# Skaarhoj_BI8-1x8slim.net
KiCad netlist of a schematic drawn in EAGLE
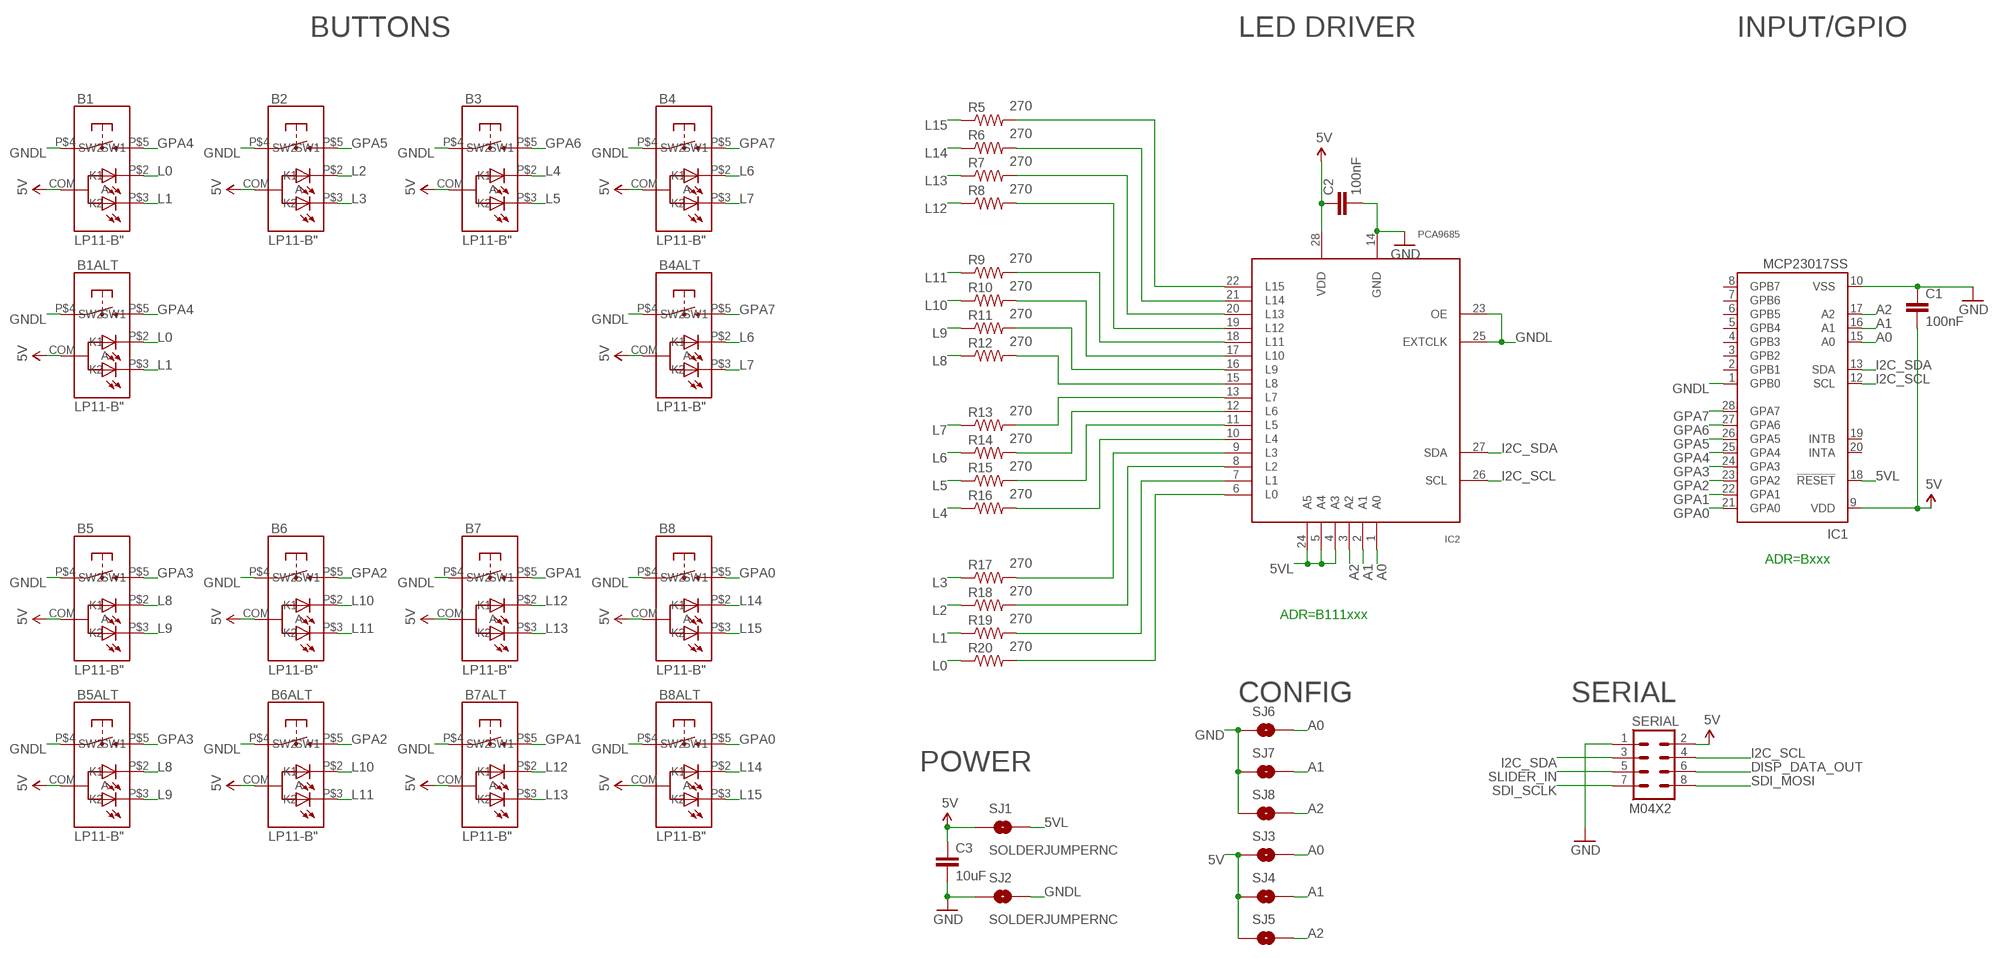
[diagram p0: schematic, sheet 1]

(export (version "E")
  (design (tool "Eeschema 10.0.6"))
  (components
    (comp (ref "B1")
      (value "LP11-B\"")
      (footprint "eagle-import:LP11")
      (libsource (lib "eagle-import") (part "LP11-B{dblquote}"))
    )
    (comp (ref "B1ALT")
      (value "LP11-B\"")
      (footprint "eagle-import:LP11")
      (libsource (lib "eagle-import") (part "LP11-B{dblquote}"))
    )
    (comp (ref "B2")
      (value "LP11-B\"")
      (footprint "eagle-import:LP11")
      (libsource (lib "eagle-import") (part "LP11-B{dblquote}"))
    )
    (comp (ref "B3")
      (value "LP11-B\"")
      (footprint "eagle-import:LP11")
      (libsource (lib "eagle-import") (part "LP11-B{dblquote}"))
    )
    (comp (ref "B4")
      (value "LP11-B\"")
      (footprint "eagle-import:LP11")
      (libsource (lib "eagle-import") (part "LP11-B{dblquote}"))
    )
    (comp (ref "B4ALT")
      (value "LP11-B\"")
      (footprint "eagle-import:LP11")
      (libsource (lib "eagle-import") (part "LP11-B{dblquote}"))
    )
    (comp (ref "B5")
      (value "LP11-B\"")
      (footprint "eagle-import:LP11")
      (libsource (lib "eagle-import") (part "LP11-B{dblquote}"))
    )
    (comp (ref "B5ALT")
      (value "LP11-B\"")
      (footprint "eagle-import:LP11")
      (libsource (lib "eagle-import") (part "LP11-B{dblquote}"))
    )
    (comp (ref "B6")
      (value "LP11-B\"")
      (footprint "eagle-import:LP11")
      (libsource (lib "eagle-import") (part "LP11-B{dblquote}"))
    )
    (comp (ref "B6ALT")
      (value "LP11-B\"")
      (footprint "eagle-import:LP11")
      (libsource (lib "eagle-import") (part "LP11-B{dblquote}"))
    )
    (comp (ref "B7")
      (value "LP11-B\"")
      (footprint "eagle-import:LP11")
      (libsource (lib "eagle-import") (part "LP11-B{dblquote}"))
    )
    (comp (ref "B7ALT")
      (value "LP11-B\"")
      (footprint "eagle-import:LP11")
      (libsource (lib "eagle-import") (part "LP11-B{dblquote}"))
    )
    (comp (ref "B8")
      (value "LP11-B\"")
      (footprint "eagle-import:LP11")
      (libsource (lib "eagle-import") (part "LP11-B{dblquote}"))
    )
    (comp (ref "B8ALT")
      (value "LP11-B\"")
      (footprint "eagle-import:LP11")
      (libsource (lib "eagle-import") (part "LP11-B{dblquote}"))
    )
    (comp (ref "C1")
      (value "100nF")
      (footprint "eagle-import:0603-CAP")
      (libsource (lib "eagle-import") (part "CAP0603-CAP"))
    )
    (comp (ref "C2")
      (value "100nF")
      (footprint "eagle-import:0603-CAP")
      (libsource (lib "eagle-import") (part "CAP0603-CAP"))
    )
    (comp (ref "C3")
      (value "10uF")
      (footprint "eagle-import:0805")
      (libsource (lib "eagle-import") (part "CAP0805"))
    )
    (comp (ref "IC1")
      (value "MCP23017SS")
      (footprint "eagle-import:SSOP28")
      (fields
        (field (name "MF") "MICROCHIP")
        (field (name "MPN") "MCP23017-E/SS")
        (field (name "MPN_1") "MCP23017-E/SS")
        (field (name "OC_FARNELL") "1467674")
        (field (name "OC_NEWARK") "31K2960")
      )
      (libsource (lib "eagle-import") (part "MCP23017SS"))
    )
    (comp (ref "IC2")
      (value "PCA9685")
      (footprint "eagle-import:TSSOP28")
      (libsource (lib "eagle-import") (part "PCA9685"))
    )
    (comp (ref "R5")
      (value "270")
      (footprint "eagle-import:0603-RES")
      (libsource (lib "eagle-import") (part "RESISTOR0603-RES"))
    )
    (comp (ref "R6")
      (value "270")
      (footprint "eagle-import:0603-RES")
      (libsource (lib "eagle-import") (part "RESISTOR0603-RES"))
    )
    (comp (ref "R7")
      (value "270")
      (footprint "eagle-import:0603-RES")
      (libsource (lib "eagle-import") (part "RESISTOR0603-RES"))
    )
    (comp (ref "R8")
      (value "270")
      (footprint "eagle-import:0603-RES")
      (libsource (lib "eagle-import") (part "RESISTOR0603-RES"))
    )
    (comp (ref "R9")
      (value "270")
      (footprint "eagle-import:0603-RES")
      (libsource (lib "eagle-import") (part "RESISTOR0603-RES"))
    )
    (comp (ref "R10")
      (value "270")
      (footprint "eagle-import:0603-RES")
      (libsource (lib "eagle-import") (part "RESISTOR0603-RES"))
    )
    (comp (ref "R11")
      (value "270")
      (footprint "eagle-import:0603-RES")
      (libsource (lib "eagle-import") (part "RESISTOR0603-RES"))
    )
    (comp (ref "R12")
      (value "270")
      (footprint "eagle-import:0603-RES")
      (libsource (lib "eagle-import") (part "RESISTOR0603-RES"))
    )
    (comp (ref "R13")
      (value "270")
      (footprint "eagle-import:0603-RES")
      (libsource (lib "eagle-import") (part "RESISTOR0603-RES"))
    )
    (comp (ref "R14")
      (value "270")
      (footprint "eagle-import:0603-RES")
      (libsource (lib "eagle-import") (part "RESISTOR0603-RES"))
    )
    (comp (ref "R15")
      (value "270")
      (footprint "eagle-import:0603-RES")
      (libsource (lib "eagle-import") (part "RESISTOR0603-RES"))
    )
    (comp (ref "R16")
      (value "270")
      (footprint "eagle-import:0603-RES")
      (libsource (lib "eagle-import") (part "RESISTOR0603-RES"))
    )
    (comp (ref "R17")
      (value "270")
      (footprint "eagle-import:0603-RES")
      (libsource (lib "eagle-import") (part "RESISTOR0603-RES"))
    )
    (comp (ref "R18")
      (value "270")
      (footprint "eagle-import:0603-RES")
      (libsource (lib "eagle-import") (part "RESISTOR0603-RES"))
    )
    (comp (ref "R19")
      (value "270")
      (footprint "eagle-import:0603-RES")
      (libsource (lib "eagle-import") (part "RESISTOR0603-RES"))
    )
    (comp (ref "R20")
      (value "270")
      (footprint "eagle-import:0603-RES")
      (libsource (lib "eagle-import") (part "RESISTOR0603-RES"))
    )
    (comp (ref "SERIAL")
      (value "M04X2")
      (footprint "eagle-import:2X4")
      (libsource (lib "eagle-import") (part "M04X2"))
    )
    (comp (ref "SJ1")
      (value "SOLDERJUMPERNC")
      (footprint "eagle-import:SJ_2S")
      (libsource (lib "eagle-import") (part "SOLDERJUMPERNC"))
    )
    (comp (ref "SJ2")
      (value "SOLDERJUMPERNC")
      (footprint "eagle-import:SJ_2S")
      (libsource (lib "eagle-import") (part "SOLDERJUMPERNC"))
    )
    (comp (ref "SJ3")
      (value "SOLDERJUMPERNC")
      (footprint "eagle-import:SJ_2S")
      (libsource (lib "eagle-import") (part "SOLDERJUMPERNC"))
    )
    (comp (ref "SJ4")
      (value "SOLDERJUMPERNC")
      (footprint "eagle-import:SJ_2S")
      (libsource (lib "eagle-import") (part "SOLDERJUMPERNC"))
    )
    (comp (ref "SJ5")
      (value "SOLDERJUMPERNC")
      (footprint "eagle-import:SJ_2S")
      (libsource (lib "eagle-import") (part "SOLDERJUMPERNC"))
    )
    (comp (ref "SJ6")
      (value "SOLDERJUMPERNC")
      (footprint "eagle-import:SJ_2S")
      (libsource (lib "eagle-import") (part "SOLDERJUMPERNC"))
    )
    (comp (ref "SJ7")
      (value "SOLDERJUMPERNC")
      (footprint "eagle-import:SJ_2S")
      (libsource (lib "eagle-import") (part "SOLDERJUMPERNC"))
    )
    (comp (ref "SJ8")
      (value "SOLDERJUMPERNC")
      (footprint "eagle-import:SJ_2S")
      (libsource (lib "eagle-import") (part "SOLDERJUMPERNC"))
    )
  )
  (nets
    (net (code "1") (name "/5VL") (class "Default")
      (node (ref "IC1") (pin "18") (pinfunction "~{RESET}_18") (pintype "input"))
      (node (ref "IC2") (pin "24") (pinfunction "A5_24") (pintype "input"))
      (node (ref "IC2") (pin "4") (pinfunction "A3_4") (pintype "input"))
      (node (ref "IC2") (pin "5") (pinfunction "A4_5") (pintype "input"))
      (node (ref "SJ1") (pin "2") (pinfunction "2_2") (pintype "passive"))
    )
    (net (code "2") (name "/A0") (class "Default")
      (node (ref "IC1") (pin "15") (pinfunction "A0_15") (pintype "input"))
      (node (ref "IC2") (pin "1") (pinfunction "A0_1") (pintype "input"))
      (node (ref "SJ3") (pin "2") (pinfunction "2_2") (pintype "passive"))
      (node (ref "SJ6") (pin "2") (pinfunction "2_2") (pintype "passive"))
    )
    (net (code "3") (name "/A1") (class "Default")
      (node (ref "IC1") (pin "16") (pinfunction "A1_16") (pintype "input"))
      (node (ref "IC2") (pin "2") (pinfunction "A1_2") (pintype "input"))
      (node (ref "SJ4") (pin "2") (pinfunction "2_2") (pintype "passive"))
      (node (ref "SJ7") (pin "2") (pinfunction "2_2") (pintype "passive"))
    )
    (net (code "4") (name "/A2") (class "Default")
      (node (ref "IC1") (pin "17") (pinfunction "A2_17") (pintype "input"))
      (node (ref "IC2") (pin "3") (pinfunction "A2_3") (pintype "input"))
      (node (ref "SJ5") (pin "2") (pinfunction "2_2") (pintype "passive"))
      (node (ref "SJ8") (pin "2") (pinfunction "2_2") (pintype "passive"))
    )
    (net (code "5") (name "/DISP_DATA_OUT") (class "Default")
      (node (ref "SERIAL") (pin "6") (pinfunction "6_6") (pintype "passive"))
    )
    (net (code "6") (name "/GNDL") (class "Default")
      (node (ref "B1") (pin "P$4") (pinfunction "SW1_P$4") (pintype "bidirectional"))
      (node (ref "B1ALT") (pin "P$4") (pinfunction "SW1_P$4") (pintype "bidirectional"))
      (node (ref "B2") (pin "P$4") (pinfunction "SW1_P$4") (pintype "bidirectional"))
      (node (ref "B3") (pin "P$4") (pinfunction "SW1_P$4") (pintype "bidirectional"))
      (node (ref "B4") (pin "P$4") (pinfunction "SW1_P$4") (pintype "bidirectional"))
      (node (ref "B4ALT") (pin "P$4") (pinfunction "SW1_P$4") (pintype "bidirectional"))
      (node (ref "B5") (pin "P$4") (pinfunction "SW1_P$4") (pintype "bidirectional"))
      (node (ref "B5ALT") (pin "P$4") (pinfunction "SW1_P$4") (pintype "bidirectional"))
      (node (ref "B6") (pin "P$4") (pinfunction "SW1_P$4") (pintype "bidirectional"))
      (node (ref "B6ALT") (pin "P$4") (pinfunction "SW1_P$4") (pintype "bidirectional"))
      (node (ref "B7") (pin "P$4") (pinfunction "SW1_P$4") (pintype "bidirectional"))
      (node (ref "B7ALT") (pin "P$4") (pinfunction "SW1_P$4") (pintype "bidirectional"))
      (node (ref "B8") (pin "P$4") (pinfunction "SW1_P$4") (pintype "bidirectional"))
      (node (ref "B8ALT") (pin "P$4") (pinfunction "SW1_P$4") (pintype "bidirectional"))
      (node (ref "IC1") (pin "1") (pinfunction "GPB0_1") (pintype "bidirectional"))
      (node (ref "IC2") (pin "23") (pinfunction "OE_23") (pintype "input"))
      (node (ref "IC2") (pin "25") (pinfunction "EXTCLK_25") (pintype "input"))
      (node (ref "SJ2") (pin "2") (pinfunction "2_2") (pintype "passive"))
    )
    (net (code "7") (name "/GPA0") (class "Default")
      (node (ref "B8") (pin "P$5") (pinfunction "SW2_P$5") (pintype "bidirectional"))
      (node (ref "B8ALT") (pin "P$5") (pinfunction "SW2_P$5") (pintype "bidirectional"))
      (node (ref "IC1") (pin "21") (pinfunction "GPA0_21") (pintype "bidirectional"))
    )
    (net (code "8") (name "/GPA1") (class "Default")
      (node (ref "B7") (pin "P$5") (pinfunction "SW2_P$5") (pintype "bidirectional"))
      (node (ref "B7ALT") (pin "P$5") (pinfunction "SW2_P$5") (pintype "bidirectional"))
      (node (ref "IC1") (pin "22") (pinfunction "GPA1_22") (pintype "bidirectional"))
    )
    (net (code "9") (name "/GPA2") (class "Default")
      (node (ref "B6") (pin "P$5") (pinfunction "SW2_P$5") (pintype "bidirectional"))
      (node (ref "B6ALT") (pin "P$5") (pinfunction "SW2_P$5") (pintype "bidirectional"))
      (node (ref "IC1") (pin "23") (pinfunction "GPA2_23") (pintype "bidirectional"))
    )
    (net (code "10") (name "/GPA3") (class "Default")
      (node (ref "B5") (pin "P$5") (pinfunction "SW2_P$5") (pintype "bidirectional"))
      (node (ref "B5ALT") (pin "P$5") (pinfunction "SW2_P$5") (pintype "bidirectional"))
      (node (ref "IC1") (pin "24") (pinfunction "GPA3_24") (pintype "bidirectional"))
    )
    (net (code "11") (name "/GPA4") (class "Default")
      (node (ref "B1") (pin "P$5") (pinfunction "SW2_P$5") (pintype "bidirectional"))
      (node (ref "B1ALT") (pin "P$5") (pinfunction "SW2_P$5") (pintype "bidirectional"))
      (node (ref "IC1") (pin "25") (pinfunction "GPA4_25") (pintype "bidirectional"))
    )
    (net (code "12") (name "/GPA5") (class "Default")
      (node (ref "B2") (pin "P$5") (pinfunction "SW2_P$5") (pintype "bidirectional"))
      (node (ref "IC1") (pin "26") (pinfunction "GPA5_26") (pintype "bidirectional"))
    )
    (net (code "13") (name "/GPA6") (class "Default")
      (node (ref "B3") (pin "P$5") (pinfunction "SW2_P$5") (pintype "bidirectional"))
      (node (ref "IC1") (pin "27") (pinfunction "GPA6_27") (pintype "bidirectional"))
    )
    (net (code "14") (name "/GPA7") (class "Default")
      (node (ref "B4") (pin "P$5") (pinfunction "SW2_P$5") (pintype "bidirectional"))
      (node (ref "B4ALT") (pin "P$5") (pinfunction "SW2_P$5") (pintype "bidirectional"))
      (node (ref "IC1") (pin "28") (pinfunction "GPA7_28") (pintype "bidirectional"))
    )
    (net (code "15") (name "/I2C_SCL") (class "Default")
      (node (ref "IC1") (pin "12") (pinfunction "SCL_12") (pintype "input"))
      (node (ref "IC2") (pin "26") (pinfunction "SCL_26") (pintype "input"))
      (node (ref "SERIAL") (pin "4") (pinfunction "4_4") (pintype "passive"))
    )
    (net (code "16") (name "/I2C_SDA") (class "Default")
      (node (ref "IC1") (pin "13") (pinfunction "SDA_13") (pintype "bidirectional"))
      (node (ref "IC2") (pin "27") (pinfunction "SDA_27") (pintype "input"))
      (node (ref "SERIAL") (pin "3") (pinfunction "3_3") (pintype "passive"))
    )
    (net (code "17") (name "/L0") (class "Default")
      (node (ref "B1") (pin "P$2") (pinfunction "K1_P$2") (pintype "bidirectional"))
      (node (ref "B1ALT") (pin "P$2") (pinfunction "K1_P$2") (pintype "bidirectional"))
      (node (ref "R20") (pin "1") (pinfunction "1_1") (pintype "passive"))
    )
    (net (code "18") (name "/L1") (class "Default")
      (node (ref "B1") (pin "P$3") (pinfunction "K2_P$3") (pintype "bidirectional"))
      (node (ref "B1ALT") (pin "P$3") (pinfunction "K2_P$3") (pintype "bidirectional"))
      (node (ref "R19") (pin "1") (pinfunction "1_1") (pintype "passive"))
    )
    (net (code "19") (name "/L2") (class "Default")
      (node (ref "B2") (pin "P$2") (pinfunction "K1_P$2") (pintype "bidirectional"))
      (node (ref "R18") (pin "1") (pinfunction "1_1") (pintype "passive"))
    )
    (net (code "20") (name "/L3") (class "Default")
      (node (ref "B2") (pin "P$3") (pinfunction "K2_P$3") (pintype "bidirectional"))
      (node (ref "R17") (pin "1") (pinfunction "1_1") (pintype "passive"))
    )
    (net (code "21") (name "/L4") (class "Default")
      (node (ref "B3") (pin "P$2") (pinfunction "K1_P$2") (pintype "bidirectional"))
      (node (ref "R16") (pin "1") (pinfunction "1_1") (pintype "passive"))
    )
    (net (code "22") (name "/L5") (class "Default")
      (node (ref "B3") (pin "P$3") (pinfunction "K2_P$3") (pintype "bidirectional"))
      (node (ref "R15") (pin "1") (pinfunction "1_1") (pintype "passive"))
    )
    (net (code "23") (name "/L6") (class "Default")
      (node (ref "B4") (pin "P$2") (pinfunction "K1_P$2") (pintype "bidirectional"))
      (node (ref "B4ALT") (pin "P$2") (pinfunction "K1_P$2") (pintype "bidirectional"))
      (node (ref "R14") (pin "1") (pinfunction "1_1") (pintype "passive"))
    )
    (net (code "24") (name "/L7") (class "Default")
      (node (ref "B4") (pin "P$3") (pinfunction "K2_P$3") (pintype "bidirectional"))
      (node (ref "B4ALT") (pin "P$3") (pinfunction "K2_P$3") (pintype "bidirectional"))
      (node (ref "R13") (pin "1") (pinfunction "1_1") (pintype "passive"))
    )
    (net (code "25") (name "/L8") (class "Default")
      (node (ref "B5") (pin "P$2") (pinfunction "K1_P$2") (pintype "bidirectional"))
      (node (ref "B5ALT") (pin "P$2") (pinfunction "K1_P$2") (pintype "bidirectional"))
      (node (ref "R12") (pin "1") (pinfunction "1_1") (pintype "passive"))
    )
    (net (code "26") (name "/L9") (class "Default")
      (node (ref "B5") (pin "P$3") (pinfunction "K2_P$3") (pintype "bidirectional"))
      (node (ref "B5ALT") (pin "P$3") (pinfunction "K2_P$3") (pintype "bidirectional"))
      (node (ref "R11") (pin "1") (pinfunction "1_1") (pintype "passive"))
    )
    (net (code "27") (name "/L10") (class "Default")
      (node (ref "B6") (pin "P$2") (pinfunction "K1_P$2") (pintype "bidirectional"))
      (node (ref "B6ALT") (pin "P$2") (pinfunction "K1_P$2") (pintype "bidirectional"))
      (node (ref "R10") (pin "1") (pinfunction "1_1") (pintype "passive"))
    )
    (net (code "28") (name "/L11") (class "Default")
      (node (ref "B6") (pin "P$3") (pinfunction "K2_P$3") (pintype "bidirectional"))
      (node (ref "B6ALT") (pin "P$3") (pinfunction "K2_P$3") (pintype "bidirectional"))
      (node (ref "R9") (pin "1") (pinfunction "1_1") (pintype "passive"))
    )
    (net (code "29") (name "/L12") (class "Default")
      (node (ref "B7") (pin "P$2") (pinfunction "K1_P$2") (pintype "bidirectional"))
      (node (ref "B7ALT") (pin "P$2") (pinfunction "K1_P$2") (pintype "bidirectional"))
      (node (ref "R8") (pin "1") (pinfunction "1_1") (pintype "passive"))
    )
    (net (code "30") (name "/L13") (class "Default")
      (node (ref "B7") (pin "P$3") (pinfunction "K2_P$3") (pintype "bidirectional"))
      (node (ref "B7ALT") (pin "P$3") (pinfunction "K2_P$3") (pintype "bidirectional"))
      (node (ref "R7") (pin "1") (pinfunction "1_1") (pintype "passive"))
    )
    (net (code "31") (name "/L14") (class "Default")
      (node (ref "B8") (pin "P$2") (pinfunction "K1_P$2") (pintype "bidirectional"))
      (node (ref "B8ALT") (pin "P$2") (pinfunction "K1_P$2") (pintype "bidirectional"))
      (node (ref "R6") (pin "1") (pinfunction "1_1") (pintype "passive"))
    )
    (net (code "32") (name "/L15") (class "Default")
      (node (ref "B8") (pin "P$3") (pinfunction "K2_P$3") (pintype "bidirectional"))
      (node (ref "B8ALT") (pin "P$3") (pinfunction "K2_P$3") (pintype "bidirectional"))
      (node (ref "R5") (pin "1") (pinfunction "1_1") (pintype "passive"))
    )
    (net (code "33") (name "/SDI_MOSI") (class "Default")
      (node (ref "SERIAL") (pin "8") (pinfunction "8_8") (pintype "passive"))
    )
    (net (code "34") (name "/SDI_SCLK") (class "Default")
      (node (ref "SERIAL") (pin "7") (pinfunction "7_7") (pintype "passive"))
    )
    (net (code "35") (name "/SLIDER_IN") (class "Default")
      (node (ref "SERIAL") (pin "5") (pinfunction "5_5") (pintype "passive"))
    )
    (net (code "36") (name "5V") (class "Default")
      (node (ref "B1") (pin "COM") (pinfunction "A_COM") (pintype "bidirectional"))
      (node (ref "B1ALT") (pin "COM") (pinfunction "A_COM") (pintype "bidirectional"))
      (node (ref "B2") (pin "COM") (pinfunction "A_COM") (pintype "bidirectional"))
      (node (ref "B3") (pin "COM") (pinfunction "A_COM") (pintype "bidirectional"))
      (node (ref "B4") (pin "COM") (pinfunction "A_COM") (pintype "bidirectional"))
      (node (ref "B4ALT") (pin "COM") (pinfunction "A_COM") (pintype "bidirectional"))
      (node (ref "B5") (pin "COM") (pinfunction "A_COM") (pintype "bidirectional"))
      (node (ref "B5ALT") (pin "COM") (pinfunction "A_COM") (pintype "bidirectional"))
      (node (ref "B6") (pin "COM") (pinfunction "A_COM") (pintype "bidirectional"))
      (node (ref "B6ALT") (pin "COM") (pinfunction "A_COM") (pintype "bidirectional"))
      (node (ref "B7") (pin "COM") (pinfunction "A_COM") (pintype "bidirectional"))
      (node (ref "B7ALT") (pin "COM") (pinfunction "A_COM") (pintype "bidirectional"))
      (node (ref "B8") (pin "COM") (pinfunction "A_COM") (pintype "bidirectional"))
      (node (ref "B8ALT") (pin "COM") (pinfunction "A_COM") (pintype "bidirectional"))
      (node (ref "C1") (pin "2") (pinfunction "2_2") (pintype "passive"))
      (node (ref "C2") (pin "1") (pinfunction "1_1") (pintype "passive"))
      (node (ref "C3") (pin "1") (pinfunction "1_1") (pintype "passive"))
      (node (ref "IC1") (pin "9") (pinfunction "VDD_9") (pintype "power_in"))
      (node (ref "IC2") (pin "28") (pinfunction "VDD_28") (pintype "power_in"))
      (node (ref "SERIAL") (pin "2") (pinfunction "2_2") (pintype "passive"))
      (node (ref "SJ1") (pin "1") (pinfunction "1_1") (pintype "passive"))
      (node (ref "SJ3") (pin "1") (pinfunction "1_1") (pintype "passive"))
      (node (ref "SJ4") (pin "1") (pinfunction "1_1") (pintype "passive"))
      (node (ref "SJ5") (pin "1") (pinfunction "1_1") (pintype "passive"))
    )
    (net (code "37") (name "GND") (class "Default")
      (node (ref "C1") (pin "1") (pinfunction "1_1") (pintype "passive"))
      (node (ref "C2") (pin "2") (pinfunction "2_2") (pintype "passive"))
      (node (ref "C3") (pin "2") (pinfunction "2_2") (pintype "passive"))
      (node (ref "IC1") (pin "10") (pinfunction "VSS_10") (pintype "power_in"))
      (node (ref "IC2") (pin "14") (pinfunction "GND_14") (pintype "power_in"))
      (node (ref "SERIAL") (pin "1") (pinfunction "1_1") (pintype "passive"))
      (node (ref "SJ2") (pin "1") (pinfunction "1_1") (pintype "passive"))
      (node (ref "SJ6") (pin "1") (pinfunction "1_1") (pintype "passive"))
      (node (ref "SJ7") (pin "1") (pinfunction "1_1") (pintype "passive"))
      (node (ref "SJ8") (pin "1") (pinfunction "1_1") (pintype "passive"))
    )
    (net (code "38") (name "Net-(IC2-L0)") (class "Default")
      (node (ref "IC2") (pin "6") (pinfunction "L0_6") (pintype "output"))
      (node (ref "R20") (pin "2") (pinfunction "2_2") (pintype "passive"))
    )
    (net (code "39") (name "Net-(IC2-L1)") (class "Default")
      (node (ref "IC2") (pin "7") (pinfunction "L1_7") (pintype "output"))
      (node (ref "R19") (pin "2") (pinfunction "2_2") (pintype "passive"))
    )
    (net (code "40") (name "Net-(IC2-L2)") (class "Default")
      (node (ref "IC2") (pin "8") (pinfunction "L2_8") (pintype "output"))
      (node (ref "R18") (pin "2") (pinfunction "2_2") (pintype "passive"))
    )
    (net (code "41") (name "Net-(IC2-L3)") (class "Default")
      (node (ref "IC2") (pin "9") (pinfunction "L3_9") (pintype "output"))
      (node (ref "R17") (pin "2") (pinfunction "2_2") (pintype "passive"))
    )
    (net (code "42") (name "Net-(IC2-L4)") (class "Default")
      (node (ref "IC2") (pin "10") (pinfunction "L4_10") (pintype "output"))
      (node (ref "R16") (pin "2") (pinfunction "2_2") (pintype "passive"))
    )
    (net (code "43") (name "Net-(IC2-L5)") (class "Default")
      (node (ref "IC2") (pin "11") (pinfunction "L5_11") (pintype "output"))
      (node (ref "R15") (pin "2") (pinfunction "2_2") (pintype "passive"))
    )
    (net (code "44") (name "Net-(IC2-L6)") (class "Default")
      (node (ref "IC2") (pin "12") (pinfunction "L6_12") (pintype "output"))
      (node (ref "R14") (pin "2") (pinfunction "2_2") (pintype "passive"))
    )
    (net (code "45") (name "Net-(IC2-L7)") (class "Default")
      (node (ref "IC2") (pin "13") (pinfunction "L7_13") (pintype "output"))
      (node (ref "R13") (pin "2") (pinfunction "2_2") (pintype "passive"))
    )
    (net (code "46") (name "Net-(IC2-L8)") (class "Default")
      (node (ref "IC2") (pin "15") (pinfunction "L8_15") (pintype "output"))
      (node (ref "R12") (pin "2") (pinfunction "2_2") (pintype "passive"))
    )
    (net (code "47") (name "Net-(IC2-L9)") (class "Default")
      (node (ref "IC2") (pin "16") (pinfunction "L9_16") (pintype "output"))
      (node (ref "R11") (pin "2") (pinfunction "2_2") (pintype "passive"))
    )
    (net (code "48") (name "Net-(IC2-L10)") (class "Default")
      (node (ref "IC2") (pin "17") (pinfunction "L10_17") (pintype "output"))
      (node (ref "R10") (pin "2") (pinfunction "2_2") (pintype "passive"))
    )
    (net (code "49") (name "Net-(IC2-L11)") (class "Default")
      (node (ref "IC2") (pin "18") (pinfunction "L11_18") (pintype "output"))
      (node (ref "R9") (pin "2") (pinfunction "2_2") (pintype "passive"))
    )
    (net (code "50") (name "Net-(IC2-L12)") (class "Default")
      (node (ref "IC2") (pin "19") (pinfunction "L12_19") (pintype "output"))
      (node (ref "R8") (pin "2") (pinfunction "2_2") (pintype "passive"))
    )
    (net (code "51") (name "Net-(IC2-L13)") (class "Default")
      (node (ref "IC2") (pin "20") (pinfunction "L13_20") (pintype "output"))
      (node (ref "R7") (pin "2") (pinfunction "2_2") (pintype "passive"))
    )
    (net (code "52") (name "Net-(IC2-L14)") (class "Default")
      (node (ref "IC2") (pin "21") (pinfunction "L14_21") (pintype "output"))
      (node (ref "R6") (pin "2") (pinfunction "2_2") (pintype "passive"))
    )
    (net (code "53") (name "Net-(IC2-L15)") (class "Default")
      (node (ref "IC2") (pin "22") (pinfunction "L15_22") (pintype "output"))
      (node (ref "R5") (pin "2") (pinfunction "2_2") (pintype "passive"))
    )
    (net (code "54") (name "unconnected-(IC1-GPB1-Pad2)") (class "Default")
      (node (ref "IC1") (pin "2") (pinfunction "GPB1_2") (pintype "bidirectional"))
    )
    (net (code "55") (name "unconnected-(IC1-GPB2-Pad3)") (class "Default")
      (node (ref "IC1") (pin "3") (pinfunction "GPB2_3") (pintype "bidirectional"))
    )
    (net (code "56") (name "unconnected-(IC1-GPB3-Pad4)") (class "Default")
      (node (ref "IC1") (pin "4") (pinfunction "GPB3_4") (pintype "bidirectional"))
    )
    (net (code "57") (name "unconnected-(IC1-GPB4-Pad5)") (class "Default")
      (node (ref "IC1") (pin "5") (pinfunction "GPB4_5") (pintype "bidirectional"))
    )
    (net (code "58") (name "unconnected-(IC1-GPB5-Pad6)") (class "Default")
      (node (ref "IC1") (pin "6") (pinfunction "GPB5_6") (pintype "bidirectional"))
    )
    (net (code "59") (name "unconnected-(IC1-GPB6-Pad7)") (class "Default")
      (node (ref "IC1") (pin "7") (pinfunction "GPB6_7") (pintype "bidirectional"))
    )
    (net (code "60") (name "unconnected-(IC1-GPB7-Pad8)") (class "Default")
      (node (ref "IC1") (pin "8") (pinfunction "GPB7_8") (pintype "bidirectional"))
    )
    (net (code "61") (name "unconnected-(IC1-INTA-Pad20)") (class "Default")
      (node (ref "IC1") (pin "20") (pinfunction "INTA_20") (pintype "output"))
    )
    (net (code "62") (name "unconnected-(IC1-INTB-Pad19)") (class "Default")
      (node (ref "IC1") (pin "19") (pinfunction "INTB_19") (pintype "output"))
    )
  )
)
